# Sheet1.net
KiCad netlist of a schematic drawn in Altium Designer
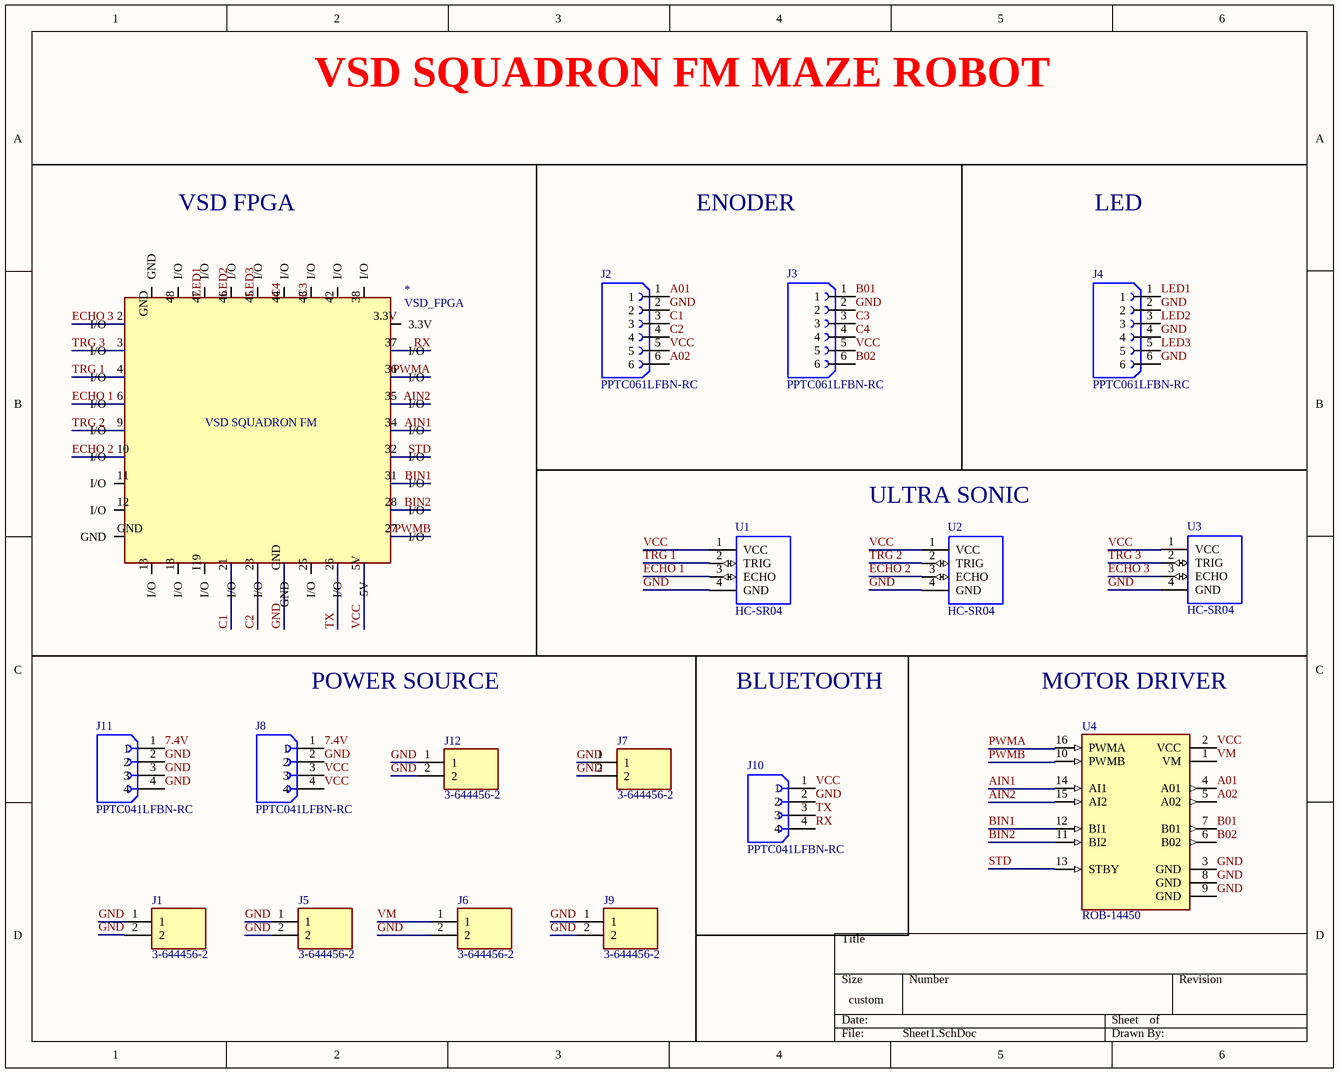
[diagram p0: Sheet1.SchDoc]

(export (version "E")
  (design (tool "Eeschema 10.0.6"))
  (components
    (comp (ref "*")
      (value "VSD_FPGA")
      (footprint "VSD_FPGA2")
      (description "VSD SQUADROM FM FPGA")
      (libsource (lib "Schlib1") (part "VSD_FPGA"))
    )
    (comp (ref "J1")
      (value "3-644456-2")
      (footprint "TE_3-644456-2")
      (description "HEADER ASSEMBLY, NARROW, MTA-100, 2 POSITION, STRAIGHT ¦ TE Connectivity 3-644456-2")
      (fields (field (name "MF") "TE Connectivity"))
      (libsource (lib "3-644456-2 (1)") (part "3-644456-2"))
    )
    (comp (ref "J2")
      (value "PPTC061LFBN-RC")
      (footprint "SULLINS_PPTC061LFBN-RC")
      (description "6 Position Total Single Row 2.54 mm Pitch Straight Female Header")
      (fields (field (name "MF") "Sullins Connector Solutions") (field (name "MP") "PPTC061LFBNRC"))
      (libsource (lib "PPTC061LFBN-RC") (part "PPTC061LFBN-RC"))
    )
    (comp (ref "J3")
      (value "PPTC061LFBN-RC")
      (footprint "SULLINS_PPTC061LFBN-RC")
      (description "6 Position Total Single Row 2.54 mm Pitch Straight Female Header")
      (fields (field (name "MF") "Sullins Connector Solutions") (field (name "MP") "PPTC061LFBNRC"))
      (libsource (lib "PPTC061LFBN-RC") (part "PPTC061LFBN-RC"))
    )
    (comp (ref "J4")
      (value "PPTC061LFBN-RC")
      (footprint "SULLINS_PPTC061LFBN-RC")
      (description "6 Position Total Single Row 2.54 mm Pitch Straight Female Header")
      (fields (field (name "MF") "Sullins Connector Solutions") (field (name "MP") "PPTC061LFBNRC"))
      (libsource (lib "PPTC061LFBN-RC") (part "PPTC061LFBN-RC"))
    )
    (comp (ref "J5")
      (value "3-644456-2")
      (footprint "TE_3-644456-2")
      (description "HEADER ASSEMBLY, NARROW, MTA-100, 2 POSITION, STRAIGHT ¦ TE Connectivity 3-644456-2")
      (fields (field (name "MF") "TE Connectivity"))
      (libsource (lib "3-644456-2 (1)") (part "3-644456-2"))
    )
    (comp (ref "J6")
      (value "3-644456-2")
      (footprint "TE_3-644456-2")
      (description "HEADER ASSEMBLY, NARROW, MTA-100, 2 POSITION, STRAIGHT ¦ TE Connectivity 3-644456-2")
      (fields (field (name "MF") "TE Connectivity"))
      (libsource (lib "3-644456-2 (1)") (part "3-644456-2"))
    )
    (comp (ref "J7")
      (value "3-644456-2")
      (footprint "TE_3-644456-2")
      (description "HEADER ASSEMBLY, NARROW, MTA-100, 2 POSITION, STRAIGHT ¦ TE Connectivity 3-644456-2")
      (fields (field (name "MF") "TE Connectivity"))
      (libsource (lib "3-644456-2 (1)") (part "3-644456-2"))
    )
    (comp (ref "J8")
      (value "PPTC041LFBN-RC")
      (footprint "SULLINS_PPTC041LFBN-RC")
      (description "4 Position Header Connector 0.100 (2.54mm) Through Hole Tin")
      (fields (field (name "MF") "Sullins Connector"))
      (libsource (lib "PPTC041LFBN-RC") (part "PPTC041LFBN-RC"))
    )
    (comp (ref "J9")
      (value "3-644456-2")
      (footprint "TE_3-644456-2")
      (description "HEADER ASSEMBLY, NARROW, MTA-100, 2 POSITION, STRAIGHT ¦ TE Connectivity 3-644456-2")
      (fields (field (name "MF") "TE Connectivity"))
      (libsource (lib "3-644456-2 (1)") (part "3-644456-2"))
    )
    (comp (ref "J10")
      (value "PPTC041LFBN-RC")
      (footprint "SULLINS_PPTC041LFBN-RC")
      (description "4 Position Header Connector 0.100 (2.54mm) Through Hole Tin")
      (fields (field (name "MF") "Sullins Connector"))
      (libsource (lib "PPTC041LFBN-RC") (part "PPTC041LFBN-RC"))
    )
    (comp (ref "J11")
      (value "PPTC041LFBN-RC")
      (footprint "SULLINS_PPTC041LFBN-RC")
      (description "4 Position Header Connector 0.100 (2.54mm) Through Hole Tin")
      (fields (field (name "MF") "Sullins Connector"))
      (libsource (lib "PPTC041LFBN-RC") (part "PPTC041LFBN-RC"))
    )
    (comp (ref "J12")
      (value "3-644456-2")
      (footprint "TE_3-644456-2")
      (description "HEADER ASSEMBLY, NARROW, MTA-100, 2 POSITION, STRAIGHT ¦ TE Connectivity 3-644456-2")
      (fields (field (name "MF") "TE Connectivity"))
      (libsource (lib "3-644456-2 (1)") (part "3-644456-2"))
    )
    (comp (ref "U1")
      (value "HC-SR04")
      (footprint "XCVR_HC-SR04")
      (description "Ultrasonic Sensor Module")
      (libsource (lib "HC-SR04") (part "HC-SR04"))
    )
    (comp (ref "U2")
      (value "HC-SR04")
      (footprint "XCVR_HC-SR04")
      (description "Ultrasonic Sensor Module")
      (libsource (lib "HC-SR04") (part "HC-SR04"))
    )
    (comp (ref "U3")
      (value "HC-SR04")
      (footprint "XCVR_HC-SR04")
      (description "Ultrasonic Sensor Module")
      (libsource (lib "HC-SR04") (part "HC-SR04"))
    )
    (comp (ref "U4")
      (value "ROB-14450")
      (footprint "MODULE_ROB-14450")
      (description "TB6612FNG Motor Controller/Driver Power Management Evaluation Board")
      (fields (field (name "MF") "SparkFun Electronics"))
      (libsource (lib "ROB-14450") (part "ROB-14450"))
    )
  )
  (nets
    (net (code "1") (name "/7.4V") (class "Default")
      (node (ref "J11") (pin "1") (pinfunction "1_1") (pintype "passive"))
      (node (ref "J8") (pin "1") (pinfunction "1_1") (pintype "passive"))
    )
    (net (code "2") (name "/A01") (class "Default")
      (node (ref "J2") (pin "1") (pinfunction "1_1") (pintype "passive"))
      (node (ref "U4") (pin "4") (pinfunction "A01_4") (pintype "output"))
    )
    (net (code "3") (name "/A02") (class "Default")
      (node (ref "J2") (pin "6") (pinfunction "6_6") (pintype "passive"))
      (node (ref "U4") (pin "5") (pinfunction "A02_5") (pintype "output"))
    )
    (net (code "4") (name "/AIN1") (class "Default")
      (node (ref "*") (pin "34") (pinfunction "I/O_34") (pintype "bidirectional"))
      (node (ref "U4") (pin "14") (pinfunction "AI1_14") (pintype "input"))
    )
    (net (code "5") (name "/AIN2") (class "Default")
      (node (ref "*") (pin "35") (pinfunction "I/O_35") (pintype "bidirectional"))
      (node (ref "U4") (pin "15") (pinfunction "AI2_15") (pintype "input"))
    )
    (net (code "6") (name "/B01") (class "Default")
      (node (ref "J3") (pin "1") (pinfunction "1_1") (pintype "passive"))
      (node (ref "U4") (pin "7") (pinfunction "B01_7") (pintype "output"))
    )
    (net (code "7") (name "/B02") (class "Default")
      (node (ref "J3") (pin "6") (pinfunction "6_6") (pintype "passive"))
      (node (ref "U4") (pin "6") (pinfunction "B02_6") (pintype "output"))
    )
    (net (code "8") (name "/BIN1") (class "Default")
      (node (ref "*") (pin "31") (pinfunction "I/O_31") (pintype "bidirectional"))
      (node (ref "U4") (pin "12") (pinfunction "BI1_12") (pintype "input"))
    )
    (net (code "9") (name "/BIN2") (class "Default")
      (node (ref "*") (pin "28") (pinfunction "I/O_28") (pintype "bidirectional"))
      (node (ref "U4") (pin "11") (pinfunction "BI2_11") (pintype "input"))
    )
    (net (code "10") (name "/C1") (class "Default")
      (node (ref "*") (pin "21") (pinfunction "I/O_21") (pintype "bidirectional"))
      (node (ref "J2") (pin "3") (pinfunction "3_3") (pintype "passive"))
    )
    (net (code "11") (name "/C2") (class "Default")
      (node (ref "*") (pin "23") (pinfunction "I/O_23") (pintype "bidirectional"))
      (node (ref "J2") (pin "4") (pinfunction "4_4") (pintype "passive"))
    )
    (net (code "12") (name "/C3") (class "Default")
      (node (ref "*") (pin "43") (pinfunction "I/O_43") (pintype "bidirectional"))
      (node (ref "J3") (pin "3") (pinfunction "3_3") (pintype "passive"))
    )
    (net (code "13") (name "/C4") (class "Default")
      (node (ref "*") (pin "44") (pinfunction "I/O_44") (pintype "bidirectional"))
      (node (ref "J3") (pin "4") (pinfunction "4_4") (pintype "passive"))
    )
    (net (code "14") (name "/ECHO 1") (class "Default")
      (node (ref "*") (pin "6") (pinfunction "I/O_6") (pintype "bidirectional"))
      (node (ref "U1") (pin "3") (pinfunction "ECHO_3") (pintype "bidirectional"))
    )
    (net (code "15") (name "/ECHO 2") (class "Default")
      (node (ref "*") (pin "10") (pinfunction "I/O_10") (pintype "bidirectional"))
      (node (ref "U2") (pin "3") (pinfunction "ECHO_3") (pintype "bidirectional"))
    )
    (net (code "16") (name "/ECHO 3") (class "Default")
      (node (ref "*") (pin "2") (pinfunction "I/O_2") (pintype "bidirectional"))
      (node (ref "U3") (pin "3") (pinfunction "ECHO_3") (pintype "bidirectional"))
    )
    (net (code "17") (name "/GND") (class "Default")
      (node (ref "*") (pin "GND") (pinfunction "GND_GND") (pintype "passive"))
      (node (ref "J1") (pin "1") (pinfunction "1_1") (pintype "passive"))
      (node (ref "J1") (pin "2") (pinfunction "2_2") (pintype "passive"))
      (node (ref "J10") (pin "2") (pinfunction "2_2") (pintype "passive"))
      (node (ref "J11") (pin "2") (pinfunction "2_2") (pintype "passive"))
      (node (ref "J11") (pin "3") (pinfunction "3_3") (pintype "passive"))
      (node (ref "J11") (pin "4") (pinfunction "4_4") (pintype "passive"))
      (node (ref "J12") (pin "1") (pinfunction "1_1") (pintype "passive"))
      (node (ref "J12") (pin "2") (pinfunction "2_2") (pintype "passive"))
      (node (ref "J2") (pin "2") (pinfunction "2_2") (pintype "passive"))
      (node (ref "J3") (pin "2") (pinfunction "2_2") (pintype "passive"))
      (node (ref "J4") (pin "2") (pinfunction "2_2") (pintype "passive"))
      (node (ref "J4") (pin "4") (pinfunction "4_4") (pintype "passive"))
      (node (ref "J4") (pin "6") (pinfunction "6_6") (pintype "passive"))
      (node (ref "J5") (pin "1") (pinfunction "1_1") (pintype "passive"))
      (node (ref "J5") (pin "2") (pinfunction "2_2") (pintype "passive"))
      (node (ref "J6") (pin "2") (pinfunction "2_2") (pintype "passive"))
      (node (ref "J7") (pin "1") (pinfunction "1_1") (pintype "passive"))
      (node (ref "J7") (pin "2") (pinfunction "2_2") (pintype "passive"))
      (node (ref "J8") (pin "2") (pinfunction "2_2") (pintype "passive"))
      (node (ref "J9") (pin "1") (pinfunction "1_1") (pintype "passive"))
      (node (ref "J9") (pin "2") (pinfunction "2_2") (pintype "passive"))
      (node (ref "U1") (pin "4") (pinfunction "GND_4") (pintype "power_in"))
      (node (ref "U2") (pin "4") (pinfunction "GND_4") (pintype "power_in"))
      (node (ref "U3") (pin "4") (pinfunction "GND_4") (pintype "power_in"))
      (node (ref "U4") (pin "3") (pinfunction "GND_3") (pintype "power_in"))
      (node (ref "U4") (pin "8") (pinfunction "GND_8") (pintype "power_in"))
      (node (ref "U4") (pin "9") (pinfunction "GND_9") (pintype "power_in"))
    )
    (net (code "18") (name "/LED1") (class "Default")
      (node (ref "*") (pin "47") (pinfunction "I/O_47") (pintype "bidirectional"))
      (node (ref "J4") (pin "1") (pinfunction "1_1") (pintype "passive"))
    )
    (net (code "19") (name "/LED2") (class "Default")
      (node (ref "*") (pin "46") (pinfunction "I/O_46") (pintype "bidirectional"))
      (node (ref "J4") (pin "3") (pinfunction "3_3") (pintype "passive"))
    )
    (net (code "20") (name "/LED3") (class "Default")
      (node (ref "*") (pin "45") (pinfunction "I/O_45") (pintype "bidirectional"))
      (node (ref "J4") (pin "5") (pinfunction "5_5") (pintype "passive"))
    )
    (net (code "21") (name "/PWMA") (class "Default")
      (node (ref "*") (pin "36") (pinfunction "I/O_36") (pintype "bidirectional"))
      (node (ref "U4") (pin "16") (pinfunction "PWMA_16") (pintype "input"))
    )
    (net (code "22") (name "/PWMB") (class "Default")
      (node (ref "*") (pin "27") (pinfunction "I/O_27") (pintype "bidirectional"))
      (node (ref "U4") (pin "10") (pinfunction "PWMB_10") (pintype "input"))
    )
    (net (code "23") (name "/RX") (class "Default")
      (node (ref "*") (pin "37") (pinfunction "I/O_37") (pintype "bidirectional"))
      (node (ref "J10") (pin "4") (pinfunction "4_4") (pintype "passive"))
    )
    (net (code "24") (name "/STD") (class "Default")
      (node (ref "*") (pin "32") (pinfunction "I/O_32") (pintype "bidirectional"))
      (node (ref "U4") (pin "13") (pinfunction "STBY_13") (pintype "input"))
    )
    (net (code "25") (name "/TRG 1") (class "Default")
      (node (ref "*") (pin "4") (pinfunction "I/O_4") (pintype "bidirectional"))
      (node (ref "U1") (pin "2") (pinfunction "TRIG_2") (pintype "bidirectional"))
    )
    (net (code "26") (name "/TRG 2") (class "Default")
      (node (ref "*") (pin "9") (pinfunction "I/O_9") (pintype "bidirectional"))
      (node (ref "U2") (pin "2") (pinfunction "TRIG_2") (pintype "bidirectional"))
    )
    (net (code "27") (name "/TRG 3") (class "Default")
      (node (ref "*") (pin "3") (pinfunction "I/O_3") (pintype "bidirectional"))
      (node (ref "U3") (pin "2") (pinfunction "TRIG_2") (pintype "bidirectional"))
    )
    (net (code "28") (name "/TX") (class "Default")
      (node (ref "*") (pin "26") (pinfunction "I/O_26") (pintype "bidirectional"))
      (node (ref "J10") (pin "3") (pinfunction "3_3") (pintype "passive"))
    )
    (net (code "29") (name "/VCC") (class "Default")
      (node (ref "*") (pin "5V") (pinfunction "5V_5V") (pintype "passive"))
      (node (ref "J10") (pin "1") (pinfunction "1_1") (pintype "passive"))
      (node (ref "J2") (pin "5") (pinfunction "5_5") (pintype "passive"))
      (node (ref "J3") (pin "5") (pinfunction "5_5") (pintype "passive"))
      (node (ref "J8") (pin "3") (pinfunction "3_3") (pintype "passive"))
      (node (ref "J8") (pin "4") (pinfunction "4_4") (pintype "passive"))
      (node (ref "U1") (pin "1") (pinfunction "VCC_1") (pintype "power_in"))
      (node (ref "U2") (pin "1") (pinfunction "VCC_1") (pintype "power_in"))
      (node (ref "U3") (pin "1") (pinfunction "VCC_1") (pintype "power_in"))
      (node (ref "U4") (pin "2") (pinfunction "VCC_2") (pintype "power_in"))
    )
    (net (code "30") (name "/VM") (class "Default")
      (node (ref "J6") (pin "1") (pinfunction "1_1") (pintype "passive"))
      (node (ref "U4") (pin "1") (pinfunction "VM_1") (pintype "power_in"))
    )
    (net (code "31") (name "unconnected-(*-I{slash}O-Pad11)") (class "Default")
      (node (ref "*") (pin "11") (pinfunction "I/O_11") (pintype "bidirectional"))
    )
    (net (code "32") (name "unconnected-(*-I{slash}O-Pad12)") (class "Default")
      (node (ref "*") (pin "12") (pinfunction "I/O_12") (pintype "bidirectional"))
    )
    (net (code "33") (name "unconnected-(*-I{slash}O-Pad13)") (class "Default")
      (node (ref "*") (pin "13") (pinfunction "I/O_13") (pintype "bidirectional"))
    )
    (net (code "34") (name "unconnected-(*-I{slash}O-Pad18)") (class "Default")
      (node (ref "*") (pin "18") (pinfunction "I/O_18") (pintype "bidirectional"))
    )
    (net (code "35") (name "unconnected-(*-I{slash}O-Pad25)") (class "Default")
      (node (ref "*") (pin "25") (pinfunction "I/O_25") (pintype "bidirectional"))
    )
    (net (code "36") (name "unconnected-(*-I{slash}O-Pad38)") (class "Default")
      (node (ref "*") (pin "38") (pinfunction "I/O_38") (pintype "passive"))
    )
    (net (code "37") (name "unconnected-(*-I{slash}O-Pad42)") (class "Default")
      (node (ref "*") (pin "42") (pinfunction "I/O_42") (pintype "passive"))
    )
    (net (code "38") (name "unconnected-(*-I{slash}O-Pad48)") (class "Default")
      (node (ref "*") (pin "48") (pinfunction "I/O_48") (pintype "bidirectional"))
    )
    (net (code "39") (name "unconnected-(*-I{slash}O-PadI19)") (class "Default")
      (node (ref "*") (pin "I19") (pinfunction "I/O_I19") (pintype "bidirectional"))
    )
    (net (code "40") (name "unconnected-(*-Pad3.3V)") (class "Default")
      (node (ref "*") (pin "3.3V") (pinfunction "3.3V_3.3V") (pintype "passive"))
    )
    (net (code "41") (name "unconnected-(*-PadGND)") (class "Default")
      (node (ref "*") (pin "GND") (pinfunction "GND_GND") (pintype "passive"))
    )
    (net (code "42") (name "unconnected-(*-PadGND)_1") (class "Default")
      (node (ref "*") (pin "GND") (pinfunction "GND_GND") (pintype "passive"))
    )
  )
)
